# Sheet4.net
KiCad netlist of a schematic drawn in Altium Designer
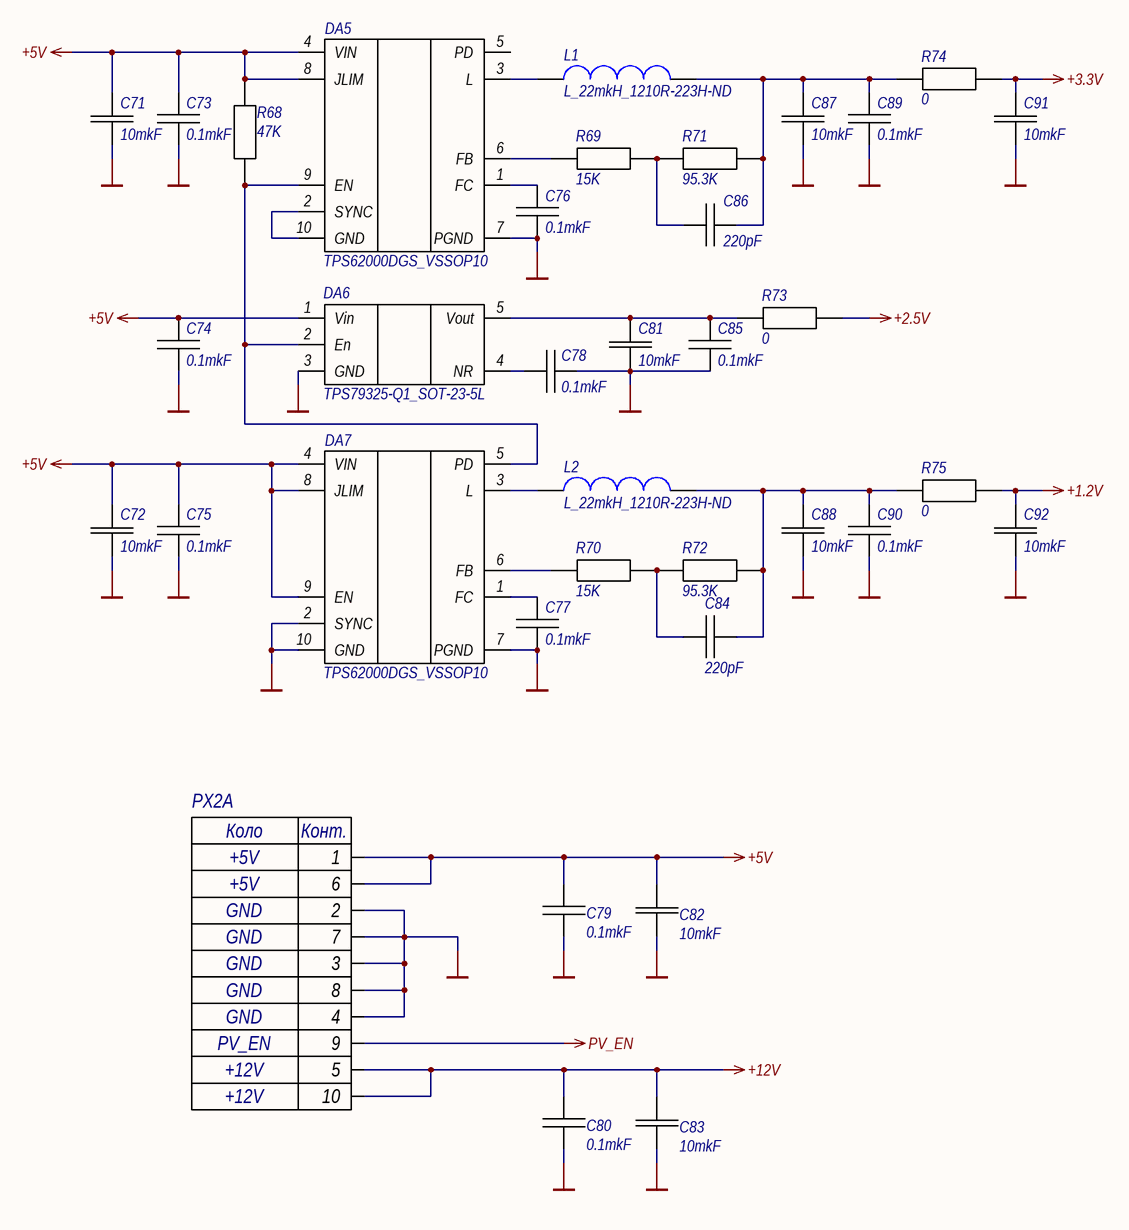
[diagram p0: Sheet4.SchDoc]

(export (version "E")
  (design (tool "Eeschema 10.0.6"))
  (components
    (comp (ref "C71")
      (value "10mkF")
      (footprint "C_1206")
      (description "C_10mkF_1206")
      (libsource (lib "АСК_1") (part "C_10mkF_1206"))
    )
    (comp (ref "C72")
      (value "10mkF")
      (footprint "C_1206")
      (description "C_10mkF_1206")
      (libsource (lib "АСК_1") (part "C_10mkF_1206"))
    )
    (comp (ref "C73")
      (value "0.1mkF")
      (footprint "C_0603")
      (description "C_0.1mkF_0603")
      (libsource (lib "АСК_1") (part "C_0.1mkF_0603"))
    )
    (comp (ref "C74")
      (value "0.1mkF")
      (footprint "C_0603")
      (description "C_0.1mkF_0603")
      (libsource (lib "АСК_1") (part "C_0.1mkF_0603"))
    )
    (comp (ref "C75")
      (value "0.1mkF")
      (footprint "C_0603")
      (description "C_0.1mkF_0603")
      (libsource (lib "АСК_1") (part "C_0.1mkF_0603"))
    )
    (comp (ref "C76")
      (value "0.1mkF")
      (footprint "C_0603")
      (description "C_0.1mkF_0603")
      (libsource (lib "АСК_1") (part "C_0.1mkF_0603"))
    )
    (comp (ref "C77")
      (value "0.1mkF")
      (footprint "C_0603")
      (description "C_0.1mkF_0603")
      (libsource (lib "АСК_1") (part "C_0.1mkF_0603"))
    )
    (comp (ref "C78")
      (value "0.1mkF")
      (footprint "C_0603")
      (description "C_0.1mkF_0603")
      (libsource (lib "АСК_1") (part "C_0.1mkF_0603"))
    )
    (comp (ref "C79")
      (value "0.1mkF")
      (footprint "C_0603")
      (description "C_0.1mkF_0603")
      (libsource (lib "АСК_1") (part "C_0.1mkF_0603"))
    )
    (comp (ref "C80")
      (value "0.1mkF")
      (footprint "C_0603")
      (description "C_0.1mkF_0603")
      (libsource (lib "АСК_1") (part "C_0.1mkF_0603"))
    )
    (comp (ref "C81")
      (value "10mkF")
      (footprint "C_1206")
      (description "C_10mkF_1206")
      (libsource (lib "АСК_1") (part "C_10mkF_1206"))
    )
    (comp (ref "C82")
      (value "10mkF")
      (footprint "C_1206")
      (description "C_10mkF_1206")
      (libsource (lib "АСК_1") (part "C_10mkF_1206"))
    )
    (comp (ref "C83")
      (value "10mkF")
      (footprint "C_1206")
      (description "C_10mkF_1206")
      (libsource (lib "АСК_1") (part "C_10mkF_1206"))
    )
    (comp (ref "C84")
      (value "220pF")
      (footprint "C_0603")
      (description "C_0.1mkF_0603")
      (libsource (lib "АСК_1") (part "C_0.1mkF_0603"))
    )
    (comp (ref "C85")
      (value "0.1mkF")
      (footprint "C_0603")
      (description "C_0.1mkF_0603")
      (libsource (lib "АСК_1") (part "C_0.1mkF_0603"))
    )
    (comp (ref "C86")
      (value "220pF")
      (footprint "C_0603")
      (description "C_0.1mkF_0603")
      (libsource (lib "АСК_1") (part "C_0.1mkF_0603"))
    )
    (comp (ref "C87")
      (value "10mkF")
      (footprint "C_1206")
      (description "C_10mkF_1206")
      (libsource (lib "АСК_1") (part "C_10mkF_1206"))
    )
    (comp (ref "C88")
      (value "10mkF")
      (footprint "C_1206")
      (description "C_10mkF_1206")
      (libsource (lib "АСК_1") (part "C_10mkF_1206"))
    )
    (comp (ref "C89")
      (value "0.1mkF")
      (footprint "C_0603")
      (description "C_0.1mkF_0603")
      (libsource (lib "АСК_1") (part "C_0.1mkF_0603"))
    )
    (comp (ref "C90")
      (value "0.1mkF")
      (footprint "C_0603")
      (description "C_0.1mkF_0603")
      (libsource (lib "АСК_1") (part "C_0.1mkF_0603"))
    )
    (comp (ref "C91")
      (value "10mkF")
      (footprint "C_1206")
      (description "C_10mkF_1206")
      (libsource (lib "АСК_1") (part "C_10mkF_1206"))
    )
    (comp (ref "C92")
      (value "10mkF")
      (footprint "C_1206")
      (description "C_10mkF_1206")
      (libsource (lib "АСК_1") (part "C_10mkF_1206"))
    )
    (comp (ref "DA5")
      (value "TPS62000DGS_VSSOP10")
      (footprint "THS4130IDGK(MSOP8)")
      (libsource (lib "АСК_1") (part "TPS62000DGS_VSSOP10"))
    )
    (comp (ref "DA6")
      (value "TPS79325-Q1_SOT-23-5L")
      (footprint "SOT95P280X110-5N")
      (libsource (lib "АСК_1") (part "TPS79325-Q1_SOT-23-5L"))
    )
    (comp (ref "DA7")
      (value "TPS62000DGS_VSSOP10")
      (footprint "THS4130IDGK(MSOP8)")
      (libsource (lib "АСК_1") (part "TPS62000DGS_VSSOP10"))
    )
    (comp (ref "L1")
      (value "L_22mkH_1210R-223H-ND")
      (footprint "1210R_IND")
      (libsource (lib "АСК_1") (part "L_22mkH_1210R-223H-ND"))
    )
    (comp (ref "L2")
      (value "L_22mkH_1210R-223H-ND")
      (footprint "1210R_IND")
      (libsource (lib "АСК_1") (part "L_22mkH_1210R-223H-ND"))
    )
    (comp (ref "PX2") (value "M80-5101042") (libsource (lib "АСК_1") (part "M80-5101042")))
    (comp (ref "R68")
      (value "47K")
      (footprint "R_1206")
      (description "R_10_1206")
      (libsource (lib "АСК_1") (part "R_10_1206"))
    )
    (comp (ref "R69")
      (value "15K")
      (footprint "R_1206")
      (description "R_10_1206")
      (libsource (lib "АСК_1") (part "R_10_1206"))
    )
    (comp (ref "R70")
      (value "15K")
      (footprint "R_1206")
      (description "R_10_1206")
      (libsource (lib "АСК_1") (part "R_10_1206"))
    )
    (comp (ref "R71")
      (value "95.3K")
      (footprint "R_1206")
      (description "R_10_1206")
      (libsource (lib "АСК_1") (part "R_10_1206"))
    )
    (comp (ref "R72")
      (value "95.3K")
      (footprint "R_1206")
      (description "R_10_1206")
      (libsource (lib "АСК_1") (part "R_10_1206"))
    )
    (comp (ref "R73")
      (value "0")
      (footprint "R_1206")
      (description "R_10_1206")
      (libsource (lib "АСК_1") (part "R_10_1206"))
    )
    (comp (ref "R74")
      (value "0")
      (footprint "R_1206")
      (description "R_10_1206")
      (libsource (lib "АСК_1") (part "R_10_1206"))
    )
    (comp (ref "R75")
      (value "0")
      (footprint "R_1206")
      (description "R_10_1206")
      (libsource (lib "АСК_1") (part "R_10_1206"))
    )
  )
  (nets
    (net (code "1") (name "+1.2V") (class "Default")
      (node (ref "C92") (pin "2") (pinfunction "2_2") (pintype "passive"))
      (node (ref "R75") (pin "1") (pinfunction "1_1") (pintype "passive"))
    )
    (net (code "2") (name "+2.5V") (class "Default")
      (node (ref "R73") (pin "1") (pinfunction "1_1") (pintype "passive"))
    )
    (net (code "3") (name "+3.3V") (class "Default")
      (node (ref "C91") (pin "2") (pinfunction "2_2") (pintype "passive"))
      (node (ref "R74") (pin "1") (pinfunction "1_1") (pintype "passive"))
    )
    (net (code "4") (name "+5V") (class "Default")
      (node (ref "C71") (pin "2") (pinfunction "2_2") (pintype "passive"))
      (node (ref "C72") (pin "2") (pinfunction "2_2") (pintype "passive"))
      (node (ref "C73") (pin "1") (pinfunction "1_1") (pintype "passive"))
      (node (ref "C74") (pin "1") (pinfunction "1_1") (pintype "passive"))
      (node (ref "C75") (pin "1") (pinfunction "1_1") (pintype "passive"))
      (node (ref "C79") (pin "1") (pinfunction "1_1") (pintype "passive"))
      (node (ref "C82") (pin "2") (pinfunction "2_2") (pintype "passive"))
      (node (ref "DA5") (pin "4") (pinfunction "VIN_4") (pintype "passive"))
      (node (ref "DA5") (pin "8") (pinfunction "JLIM_8") (pintype "passive"))
      (node (ref "DA6") (pin "1") (pinfunction "Vin_1") (pintype "passive"))
      (node (ref "DA7") (pin "4") (pinfunction "VIN_4") (pintype "passive"))
      (node (ref "DA7") (pin "8") (pinfunction "JLIM_8") (pintype "passive"))
      (node (ref "DA7") (pin "9") (pinfunction "EN_9") (pintype "passive"))
      (node (ref "PX2") (pin "1") (pinfunction "1_1") (pintype "passive"))
      (node (ref "PX2") (pin "6") (pinfunction "6_6") (pintype "passive"))
      (node (ref "R68") (pin "1") (pinfunction "1_1") (pintype "passive"))
    )
    (net (code "5") (name "+12V") (class "Default")
      (node (ref "C80") (pin "1") (pinfunction "1_1") (pintype "passive"))
      (node (ref "C83") (pin "2") (pinfunction "2_2") (pintype "passive"))
      (node (ref "PX2") (pin "10") (pinfunction "10_10") (pintype "passive"))
      (node (ref "PX2") (pin "5") (pinfunction "5_5") (pintype "passive"))
    )
    (net (code "6") (name "GND") (class "Default")
      (node (ref "C71") (pin "1") (pinfunction "1_1") (pintype "passive"))
      (node (ref "C72") (pin "1") (pinfunction "1_1") (pintype "passive"))
      (node (ref "C73") (pin "2") (pinfunction "2_2") (pintype "passive"))
      (node (ref "C74") (pin "2") (pinfunction "2_2") (pintype "passive"))
      (node (ref "C75") (pin "2") (pinfunction "2_2") (pintype "passive"))
      (node (ref "C76") (pin "2") (pinfunction "2_2") (pintype "passive"))
      (node (ref "C77") (pin "2") (pinfunction "2_2") (pintype "passive"))
      (node (ref "C78") (pin "1") (pinfunction "1_1") (pintype "passive"))
      (node (ref "C79") (pin "2") (pinfunction "2_2") (pintype "passive"))
      (node (ref "C80") (pin "2") (pinfunction "2_2") (pintype "passive"))
      (node (ref "C81") (pin "1") (pinfunction "1_1") (pintype "passive"))
      (node (ref "C82") (pin "1") (pinfunction "1_1") (pintype "passive"))
      (node (ref "C83") (pin "1") (pinfunction "1_1") (pintype "passive"))
      (node (ref "C85") (pin "2") (pinfunction "2_2") (pintype "passive"))
      (node (ref "C87") (pin "1") (pinfunction "1_1") (pintype "passive"))
      (node (ref "C88") (pin "1") (pinfunction "1_1") (pintype "passive"))
      (node (ref "C89") (pin "2") (pinfunction "2_2") (pintype "passive"))
      (node (ref "C90") (pin "2") (pinfunction "2_2") (pintype "passive"))
      (node (ref "C91") (pin "1") (pinfunction "1_1") (pintype "passive"))
      (node (ref "C92") (pin "1") (pinfunction "1_1") (pintype "passive"))
      (node (ref "DA5") (pin "7") (pinfunction "PGND_7") (pintype "passive"))
      (node (ref "DA6") (pin "3") (pinfunction "GND_3") (pintype "passive"))
      (node (ref "DA7") (pin "10") (pinfunction "GND_10") (pintype "passive"))
      (node (ref "DA7") (pin "2") (pinfunction "SYNC_2") (pintype "passive"))
      (node (ref "DA7") (pin "7") (pinfunction "PGND_7") (pintype "passive"))
      (node (ref "PX2") (pin "2") (pinfunction "2_2") (pintype "passive"))
      (node (ref "PX2") (pin "3") (pinfunction "3_3") (pintype "passive"))
      (node (ref "PX2") (pin "4") (pinfunction "4_4") (pintype "passive"))
      (node (ref "PX2") (pin "7") (pinfunction "7_7") (pintype "passive"))
      (node (ref "PX2") (pin "8") (pinfunction "8_8") (pintype "passive"))
    )
    (net (code "7") (name "Net-(C84-Pad1)") (class "Default")
      (node (ref "C84") (pin "1") (pinfunction "1_1") (pintype "passive"))
      (node (ref "R70") (pin "1") (pinfunction "1_1") (pintype "passive"))
      (node (ref "R72") (pin "1") (pinfunction "1_1") (pintype "passive"))
    )
    (net (code "8") (name "Net-(C84-Pad2)") (class "Default")
      (node (ref "C84") (pin "2") (pinfunction "2_2") (pintype "passive"))
      (node (ref "C88") (pin "2") (pinfunction "2_2") (pintype "passive"))
      (node (ref "C90") (pin "1") (pinfunction "1_1") (pintype "passive"))
      (node (ref "L2") (pin "2") (pinfunction "2_2") (pintype "passive"))
      (node (ref "R72") (pin "2") (pinfunction "2_2") (pintype "passive"))
      (node (ref "R75") (pin "2") (pinfunction "2_2") (pintype "passive"))
    )
    (net (code "9") (name "Net-(C86-Pad1)") (class "Default")
      (node (ref "C86") (pin "1") (pinfunction "1_1") (pintype "passive"))
      (node (ref "R69") (pin "1") (pinfunction "1_1") (pintype "passive"))
      (node (ref "R71") (pin "1") (pinfunction "1_1") (pintype "passive"))
    )
    (net (code "10") (name "Net-(C86-Pad2)") (class "Default")
      (node (ref "C86") (pin "2") (pinfunction "2_2") (pintype "passive"))
      (node (ref "C87") (pin "2") (pinfunction "2_2") (pintype "passive"))
      (node (ref "C89") (pin "1") (pinfunction "1_1") (pintype "passive"))
      (node (ref "L1") (pin "2") (pinfunction "2_2") (pintype "passive"))
      (node (ref "R71") (pin "2") (pinfunction "2_2") (pintype "passive"))
      (node (ref "R74") (pin "2") (pinfunction "2_2") (pintype "passive"))
    )
    (net (code "11") (name "Net-(DA5-EN)") (class "Default")
      (node (ref "DA5") (pin "9") (pinfunction "EN_9") (pintype "passive"))
      (node (ref "DA6") (pin "2") (pinfunction "En_2") (pintype "passive"))
      (node (ref "DA7") (pin "5") (pinfunction "PD_5") (pintype "passive"))
      (node (ref "R68") (pin "2") (pinfunction "2_2") (pintype "passive"))
    )
    (net (code "12") (name "Net-(DA5-FB)") (class "Default")
      (node (ref "DA5") (pin "6") (pinfunction "FB_6") (pintype "passive"))
      (node (ref "R69") (pin "2") (pinfunction "2_2") (pintype "passive"))
    )
    (net (code "13") (name "Net-(DA5-FC)") (class "Default")
      (node (ref "C76") (pin "1") (pinfunction "1_1") (pintype "passive"))
      (node (ref "DA5") (pin "1") (pinfunction "FC_1") (pintype "passive"))
    )
    (net (code "14") (name "Net-(DA5-GND)") (class "Default")
      (node (ref "DA5") (pin "10") (pinfunction "GND_10") (pintype "passive"))
      (node (ref "DA5") (pin "2") (pinfunction "SYNC_2") (pintype "passive"))
    )
    (net (code "15") (name "Net-(DA5-L)") (class "Default")
      (node (ref "DA5") (pin "3") (pinfunction "L_3") (pintype "passive"))
      (node (ref "L1") (pin "1") (pinfunction "1_1") (pintype "passive"))
    )
    (net (code "16") (name "Net-(DA6-NR)") (class "Default")
      (node (ref "C78") (pin "2") (pinfunction "2_2") (pintype "passive"))
      (node (ref "DA6") (pin "4") (pinfunction "NR_4") (pintype "passive"))
    )
    (net (code "17") (name "Net-(DA6-Vout)") (class "Default")
      (node (ref "C81") (pin "2") (pinfunction "2_2") (pintype "passive"))
      (node (ref "C85") (pin "1") (pinfunction "1_1") (pintype "passive"))
      (node (ref "DA6") (pin "5") (pinfunction "Vout_5") (pintype "passive"))
      (node (ref "R73") (pin "2") (pinfunction "2_2") (pintype "passive"))
    )
    (net (code "18") (name "Net-(DA7-FB)") (class "Default")
      (node (ref "DA7") (pin "6") (pinfunction "FB_6") (pintype "passive"))
      (node (ref "R70") (pin "2") (pinfunction "2_2") (pintype "passive"))
    )
    (net (code "19") (name "Net-(DA7-FC)") (class "Default")
      (node (ref "C77") (pin "1") (pinfunction "1_1") (pintype "passive"))
      (node (ref "DA7") (pin "1") (pinfunction "FC_1") (pintype "passive"))
    )
    (net (code "20") (name "Net-(DA7-L)") (class "Default")
      (node (ref "DA7") (pin "3") (pinfunction "L_3") (pintype "passive"))
      (node (ref "L2") (pin "1") (pinfunction "1_1") (pintype "passive"))
    )
    (net (code "21") (name "PV_EN") (class "Default")
      (node (ref "PX2") (pin "9") (pinfunction "9_9") (pintype "passive"))
    )
    (net (code "22") (name "unconnected-(DA5-PD-Pad5)") (class "Default")
      (node (ref "DA5") (pin "5") (pinfunction "PD_5") (pintype "passive"))
    )
  )
)
